# MegaMini.net
KiCad netlist of a schematic drawn in EAGLE
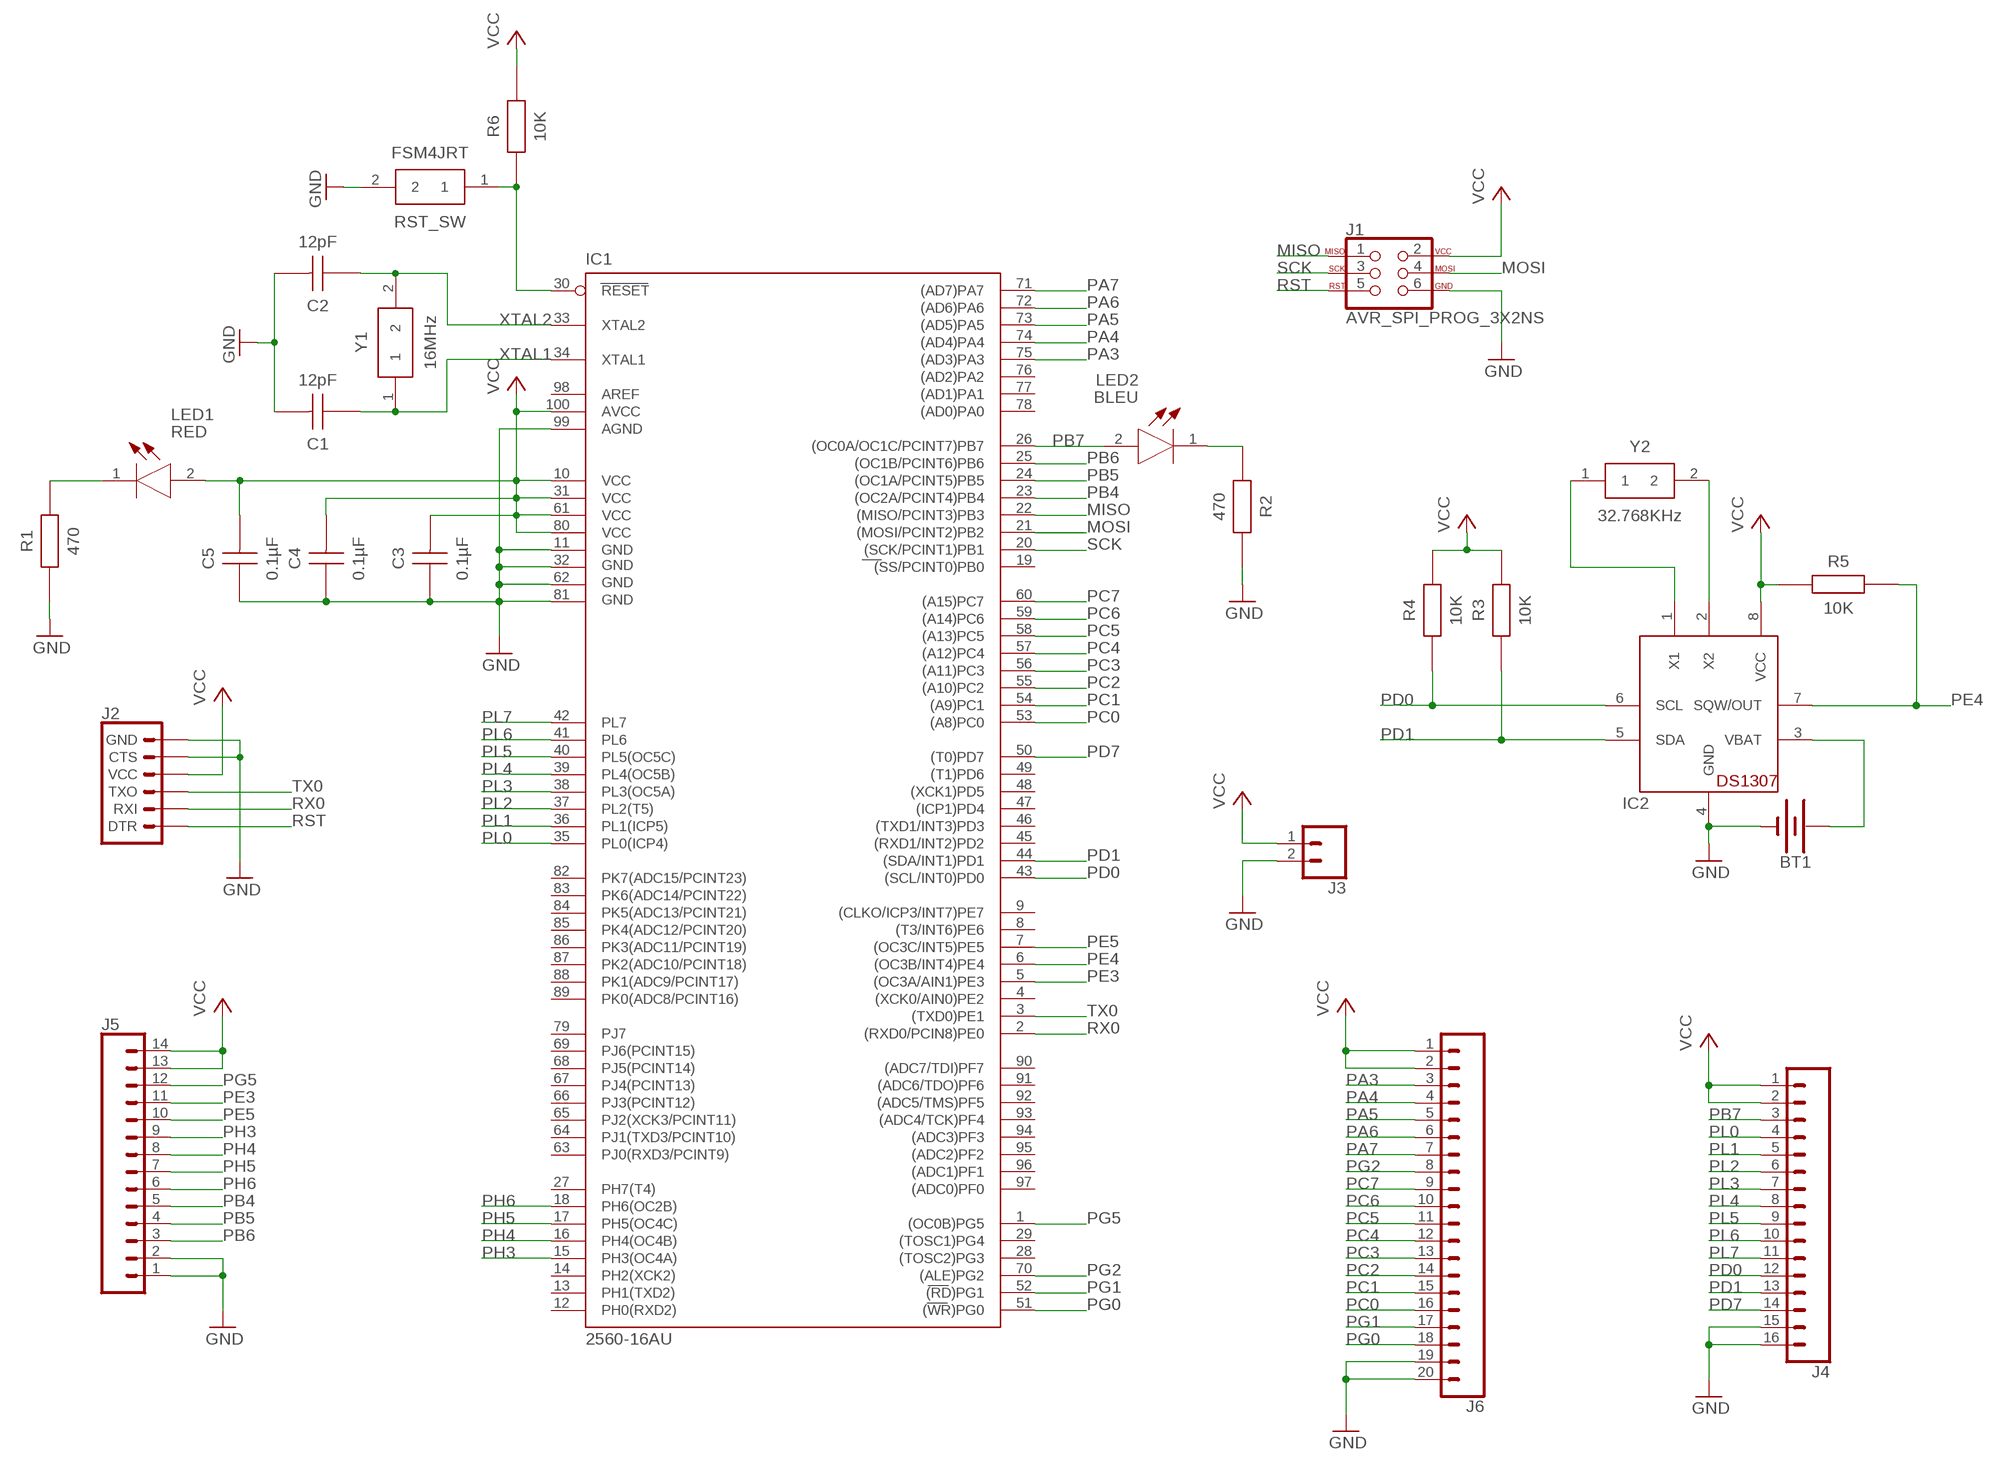
[diagram p0: schematic, sheet 1]

(export (version "E")
  (design (tool "Eeschema 10.0.6"))
  (components
    (comp (ref "BT1")
      (value "BATTERY-12MM_PTH")
      (footprint "eagle-import:BATTCON_12MM_PTH")
      (libsource (lib "eagle-import") (part "BATTERY-12MM_PTH"))
    )
    (comp (ref "C1")
      (value "12pF")
      (footprint "eagle-import:CAPC3216X88N")
      (fields
        (field (name "MANUFACTURER_PART_NUMBER") "C1206C120J5GACTU")
        (field (name "RS_PART_NUMBER") "8029986P")
      )
      (libsource (lib "eagle-import") (part "C1206C120J5GACTU"))
    )
    (comp (ref "C2")
      (value "12pF")
      (footprint "eagle-import:CAPC3216X88N")
      (fields
        (field (name "MANUFACTURER_PART_NUMBER") "C1206C120J5GACTU")
        (field (name "RS_PART_NUMBER") "8029986P")
      )
      (libsource (lib "eagle-import") (part "C1206C120J5GACTU"))
    )
    (comp (ref "C3")
      (value "0.1µF")
      (footprint "eagle-import:CAPC3216X88N")
      (fields
        (field (name "MANUFACTURER_PART_NUMBER") "C1206C104K5RACTU")
        (field (name "RS_PART_NUMBER") "2644179P")
      )
      (libsource (lib "eagle-import") (part "C1206C104K5RACTU"))
    )
    (comp (ref "C4")
      (value "0.1µF")
      (footprint "eagle-import:CAPC3216X88N")
      (fields
        (field (name "MANUFACTURER_PART_NUMBER") "C1206C104K5RACTU")
        (field (name "RS_PART_NUMBER") "2644179P")
      )
      (libsource (lib "eagle-import") (part "C1206C104K5RACTU"))
    )
    (comp (ref "C5")
      (value "0.1µF")
      (footprint "eagle-import:CAPC3216X88N")
      (fields
        (field (name "MANUFACTURER_PART_NUMBER") "C1206C104K5RACTU")
        (field (name "RS_PART_NUMBER") "2644179P")
      )
      (libsource (lib "eagle-import") (part "C1206C104K5RACTU"))
    )
    (comp (ref "IC1")
      (value "2560-16AU")
      (footprint "eagle-import:TQFP100")
      (libsource (lib "eagle-import") (part "ATMEGAAU2560-16"))
    )
    (comp (ref "IC2")
      (value "DS1307")
      (footprint "eagle-import:DIL08")
      (libsource (lib "eagle-import") (part "DS1307"))
    )
    (comp (ref "J1")
      (value "AVR_SPI_PROG_3X2NS")
      (footprint "eagle-import:2X3-NS")
      (libsource (lib "eagle-import") (part "AVR_SPI_PROG_3X2NS"))
    )
    (comp (ref "J2")
      (value "6_PIN_SERIAL_TARGET")
      (footprint "eagle-import:1X06")
      (libsource (lib "eagle-import") (part "6_PIN_SERIAL_TARGET"))
    )
    (comp (ref "J3")
      (value "CONN_02")
      (footprint "eagle-import:1X02")
      (libsource (lib "eagle-import") (part "CONN_02"))
    )
    (comp (ref "J4")
      (value "CONN_16")
      (footprint "eagle-import:1X16")
      (libsource (lib "eagle-import") (part "CONN_16"))
    )
    (comp (ref "J5")
      (value "CONN_14")
      (footprint "eagle-import:1X14")
      (libsource (lib "eagle-import") (part "CONN_14"))
    )
    (comp (ref "J6")
      (value "CONN_20")
      (footprint "eagle-import:1X20")
      (libsource (lib "eagle-import") (part "CONN_20"))
    )
    (comp (ref "LED1")
      (value "RED")
      (footprint "eagle-import:LEDC1608X80N")
      (fields (field (name "MANUFACTURER_PART_NUMBER") "150060RS75000"))
      (libsource (lib "eagle-import") (part "150060RS75000"))
    )
    (comp (ref "LED2")
      (value "BLEU")
      (footprint "eagle-import:LEDC3214X78N")
      (fields
        (field (name "MANUFACTURER_PART_NUMBER") "150120BS75000")
        (field (name "RS_PART_NUMBER") "8154243")
      )
      (libsource (lib "eagle-import") (part "150120BS75000"))
    )
    (comp (ref "R1")
      (value "470")
      (footprint "eagle-import:RESC3116X70N")
      (fields
        (field (name "MANUFACTURER_PART_NUMBER") "ERJ8ENF4700V")
        (field (name "RS_PART_NUMBER") "1142909")
      )
      (libsource (lib "eagle-import") (part "ERJ8ENF4700V"))
    )
    (comp (ref "R2")
      (value "470")
      (footprint "eagle-import:RESC3116X70N")
      (fields
        (field (name "MANUFACTURER_PART_NUMBER") "ERJ8ENF4700V")
        (field (name "RS_PART_NUMBER") "1142909")
      )
      (libsource (lib "eagle-import") (part "ERJ8ENF4700V"))
    )
    (comp (ref "R3")
      (value "10K")
      (footprint "eagle-import:RESC3116X70N")
      (fields (field (name "MANUFACTURER_PART_NUMBER") "ERJ-8ENF1002V"))
      (libsource (lib "eagle-import") (part "ERJ-8ENF1002V"))
    )
    (comp (ref "R4")
      (value "10K")
      (footprint "eagle-import:RESC3116X70N")
      (fields (field (name "MANUFACTURER_PART_NUMBER") "ERJ-8ENF1002V"))
      (libsource (lib "eagle-import") (part "ERJ-8ENF1002V"))
    )
    (comp (ref "R5")
      (value "10K")
      (footprint "eagle-import:RESC3116X70N")
      (fields (field (name "MANUFACTURER_PART_NUMBER") "ERJ-8ENF1002V"))
      (libsource (lib "eagle-import") (part "ERJ-8ENF1002V"))
    )
    (comp (ref "R6")
      (value "10K")
      (footprint "eagle-import:RESC3116X70N")
      (fields (field (name "MANUFACTURER_PART_NUMBER") "ERJ-8ENF1002V"))
      (libsource (lib "eagle-import") (part "ERJ-8ENF1002V"))
    )
    (comp (ref "RST_SW")
      (value "FSM4JRT")
      (footprint "eagle-import:FSM4JRT")
      (fields (field (name "RS_PART_NUMBER") "7182415P"))
      (libsource (lib "eagle-import") (part "FSM4JRT"))
    )
    (comp (ref "Y1")
      (value "16MHz")
      (footprint "eagle-import:FOXSDLF_120-20")
      (fields
        (field (name "MANUFACTURER_PART_NUMBER") "FOXSDLF/160-20")
        (field (name "RS_PART_NUMBER") "5476531")
      )
      (libsource (lib "eagle-import") (part "FOXSDLF_160-20"))
    )
    (comp (ref "Y2")
      (value "32.768KHz")
      (footprint "eagle-import:FC-135")
      (fields (field (name "MANUFACTURER_PART_NUMBER") "Q13FC13500004 FC-135 32.768KHZ 12.5PF"))
      (libsource (lib "eagle-import") (part "Q13FC13500004_FC-135_32.768KHZ"))
    )
  )
  (nets
    (net (code "1") (name "/MISO") (class "Default")
      (node (ref "IC1") (pin "22") (pinfunction "(MISO/PCINT3)PB3_22") (pintype "bidirectional"))
      (node (ref "J1") (pin "1") (pinfunction "1_1") (pintype "passive"))
    )
    (net (code "2") (name "/MOSI") (class "Default")
      (node (ref "IC1") (pin "21") (pinfunction "(MOSI/PCINT2)PB2_21") (pintype "bidirectional"))
      (node (ref "J1") (pin "4") (pinfunction "4_4") (pintype "passive"))
    )
    (net (code "3") (name "/PA3") (class "Default")
      (node (ref "IC1") (pin "75") (pinfunction "(AD3)PA3_75") (pintype "bidirectional"))
      (node (ref "J6") (pin "3") (pinfunction "3_3") (pintype "passive"))
    )
    (net (code "4") (name "/PA4") (class "Default")
      (node (ref "IC1") (pin "74") (pinfunction "(AD4)PA4_74") (pintype "bidirectional"))
      (node (ref "J6") (pin "4") (pinfunction "4_4") (pintype "passive"))
    )
    (net (code "5") (name "/PA5") (class "Default")
      (node (ref "IC1") (pin "73") (pinfunction "(AD5)PA5_73") (pintype "bidirectional"))
      (node (ref "J6") (pin "5") (pinfunction "5_5") (pintype "passive"))
    )
    (net (code "6") (name "/PA6") (class "Default")
      (node (ref "IC1") (pin "72") (pinfunction "(AD6)PA6_72") (pintype "bidirectional"))
      (node (ref "J6") (pin "6") (pinfunction "6_6") (pintype "passive"))
    )
    (net (code "7") (name "/PA7") (class "Default")
      (node (ref "IC1") (pin "71") (pinfunction "(AD7)PA7_71") (pintype "bidirectional"))
      (node (ref "J6") (pin "7") (pinfunction "7_7") (pintype "passive"))
    )
    (net (code "8") (name "/PB4") (class "Default")
      (node (ref "IC1") (pin "23") (pinfunction "(OC2A/PCINT4)PB4_23") (pintype "bidirectional"))
      (node (ref "J5") (pin "5") (pinfunction "5_5") (pintype "passive"))
    )
    (net (code "9") (name "/PB5") (class "Default")
      (node (ref "IC1") (pin "24") (pinfunction "(OC1A/PCINT5)PB5_24") (pintype "bidirectional"))
      (node (ref "J5") (pin "4") (pinfunction "4_4") (pintype "passive"))
    )
    (net (code "10") (name "/PB6") (class "Default")
      (node (ref "IC1") (pin "25") (pinfunction "(OC1B/PCINT6)PB6_25") (pintype "bidirectional"))
      (node (ref "J5") (pin "3") (pinfunction "3_3") (pintype "passive"))
    )
    (net (code "11") (name "/PB7") (class "Default")
      (node (ref "IC1") (pin "26") (pinfunction "(OC0A/OC1C/PCINT7)PB7_26") (pintype "bidirectional"))
      (node (ref "J4") (pin "3") (pinfunction "3_3") (pintype "passive"))
      (node (ref "LED2") (pin "2") (pinfunction "A_2") (pintype "input"))
    )
    (net (code "12") (name "/PC0") (class "Default")
      (node (ref "IC1") (pin "53") (pinfunction "(A8)PC0_53") (pintype "bidirectional"))
      (node (ref "J6") (pin "16") (pinfunction "16_16") (pintype "passive"))
    )
    (net (code "13") (name "/PC1") (class "Default")
      (node (ref "IC1") (pin "54") (pinfunction "(A9)PC1_54") (pintype "bidirectional"))
      (node (ref "J6") (pin "15") (pinfunction "15_15") (pintype "passive"))
    )
    (net (code "14") (name "/PC2") (class "Default")
      (node (ref "IC1") (pin "55") (pinfunction "(A10)PC2_55") (pintype "bidirectional"))
      (node (ref "J6") (pin "14") (pinfunction "14_14") (pintype "passive"))
    )
    (net (code "15") (name "/PC3") (class "Default")
      (node (ref "IC1") (pin "56") (pinfunction "(A11)PC3_56") (pintype "bidirectional"))
      (node (ref "J6") (pin "13") (pinfunction "13_13") (pintype "passive"))
    )
    (net (code "16") (name "/PC4") (class "Default")
      (node (ref "IC1") (pin "57") (pinfunction "(A12)PC4_57") (pintype "bidirectional"))
      (node (ref "J6") (pin "12") (pinfunction "12_12") (pintype "passive"))
    )
    (net (code "17") (name "/PC5") (class "Default")
      (node (ref "IC1") (pin "58") (pinfunction "(A13)PC5_58") (pintype "bidirectional"))
      (node (ref "J6") (pin "11") (pinfunction "11_11") (pintype "passive"))
    )
    (net (code "18") (name "/PC6") (class "Default")
      (node (ref "IC1") (pin "59") (pinfunction "(A14)PC6_59") (pintype "bidirectional"))
      (node (ref "J6") (pin "10") (pinfunction "10_10") (pintype "passive"))
    )
    (net (code "19") (name "/PC7") (class "Default")
      (node (ref "IC1") (pin "60") (pinfunction "(A15)PC7_60") (pintype "bidirectional"))
      (node (ref "J6") (pin "9") (pinfunction "9_9") (pintype "passive"))
    )
    (net (code "20") (name "/PD0") (class "Default")
      (node (ref "IC1") (pin "43") (pinfunction "(SCL/INT0)PD0_43") (pintype "bidirectional"))
      (node (ref "IC2") (pin "6") (pinfunction "SCL_6") (pintype "bidirectional"))
      (node (ref "J4") (pin "12") (pinfunction "12_12") (pintype "passive"))
      (node (ref "R4") (pin "1") (pinfunction "1_1") (pintype "bidirectional"))
    )
    (net (code "21") (name "/PD1") (class "Default")
      (node (ref "IC1") (pin "44") (pinfunction "(SDA/INT1)PD1_44") (pintype "bidirectional"))
      (node (ref "IC2") (pin "5") (pinfunction "SDA_5") (pintype "bidirectional"))
      (node (ref "J4") (pin "13") (pinfunction "13_13") (pintype "passive"))
      (node (ref "R3") (pin "1") (pinfunction "1_1") (pintype "bidirectional"))
    )
    (net (code "22") (name "/PD7") (class "Default")
      (node (ref "IC1") (pin "50") (pinfunction "(T0)PD7_50") (pintype "bidirectional"))
      (node (ref "J4") (pin "14") (pinfunction "14_14") (pintype "passive"))
    )
    (net (code "23") (name "/PE3") (class "Default")
      (node (ref "IC1") (pin "5") (pinfunction "(OC3A/AIN1)PE3_5") (pintype "bidirectional"))
      (node (ref "J5") (pin "11") (pinfunction "11_11") (pintype "passive"))
    )
    (net (code "24") (name "/PE4") (class "Default")
      (node (ref "IC1") (pin "6") (pinfunction "(OC3B/INT4)PE4_6") (pintype "bidirectional"))
      (node (ref "IC2") (pin "7") (pinfunction "SQW/OUT_7") (pintype "bidirectional"))
      (node (ref "R5") (pin "2") (pinfunction "2_2") (pintype "bidirectional"))
    )
    (net (code "25") (name "/PE5") (class "Default")
      (node (ref "IC1") (pin "7") (pinfunction "(OC3C/INT5)PE5_7") (pintype "bidirectional"))
      (node (ref "J5") (pin "10") (pinfunction "10_10") (pintype "passive"))
    )
    (net (code "26") (name "/PG0") (class "Default")
      (node (ref "IC1") (pin "51") (pinfunction "(WR)PG0_51") (pintype "bidirectional"))
      (node (ref "J6") (pin "18") (pinfunction "18_18") (pintype "passive"))
    )
    (net (code "27") (name "/PG1") (class "Default")
      (node (ref "IC1") (pin "52") (pinfunction "(RD)PG1_52") (pintype "bidirectional"))
      (node (ref "J6") (pin "17") (pinfunction "17_17") (pintype "passive"))
    )
    (net (code "28") (name "/PG2") (class "Default")
      (node (ref "IC1") (pin "70") (pinfunction "(ALE)PG2_70") (pintype "bidirectional"))
      (node (ref "J6") (pin "8") (pinfunction "8_8") (pintype "passive"))
    )
    (net (code "29") (name "/PG5") (class "Default")
      (node (ref "IC1") (pin "1") (pinfunction "(OC0B)PG5_1") (pintype "bidirectional"))
      (node (ref "J5") (pin "12") (pinfunction "12_12") (pintype "passive"))
    )
    (net (code "30") (name "/PH3") (class "Default")
      (node (ref "IC1") (pin "15") (pinfunction "PH3(OC4A)_15") (pintype "bidirectional"))
      (node (ref "J5") (pin "9") (pinfunction "9_9") (pintype "passive"))
    )
    (net (code "31") (name "/PH4") (class "Default")
      (node (ref "IC1") (pin "16") (pinfunction "PH4(OC4B)_16") (pintype "bidirectional"))
      (node (ref "J5") (pin "8") (pinfunction "8_8") (pintype "passive"))
    )
    (net (code "32") (name "/PH5") (class "Default")
      (node (ref "IC1") (pin "17") (pinfunction "PH5(OC4C)_17") (pintype "bidirectional"))
      (node (ref "J5") (pin "7") (pinfunction "7_7") (pintype "passive"))
    )
    (net (code "33") (name "/PH6") (class "Default")
      (node (ref "IC1") (pin "18") (pinfunction "PH6(OC2B)_18") (pintype "bidirectional"))
      (node (ref "J5") (pin "6") (pinfunction "6_6") (pintype "passive"))
    )
    (net (code "34") (name "/PL0") (class "Default")
      (node (ref "IC1") (pin "35") (pinfunction "PL0(ICP4)_35") (pintype "bidirectional"))
      (node (ref "J4") (pin "4") (pinfunction "4_4") (pintype "passive"))
    )
    (net (code "35") (name "/PL1") (class "Default")
      (node (ref "IC1") (pin "36") (pinfunction "PL1(ICP5)_36") (pintype "bidirectional"))
      (node (ref "J4") (pin "5") (pinfunction "5_5") (pintype "passive"))
    )
    (net (code "36") (name "/PL2") (class "Default")
      (node (ref "IC1") (pin "37") (pinfunction "PL2(T5)_37") (pintype "bidirectional"))
      (node (ref "J4") (pin "6") (pinfunction "6_6") (pintype "passive"))
    )
    (net (code "37") (name "/PL3") (class "Default")
      (node (ref "IC1") (pin "38") (pinfunction "PL3(OC5A)_38") (pintype "bidirectional"))
      (node (ref "J4") (pin "7") (pinfunction "7_7") (pintype "passive"))
    )
    (net (code "38") (name "/PL4") (class "Default")
      (node (ref "IC1") (pin "39") (pinfunction "PL4(OC5B)_39") (pintype "bidirectional"))
      (node (ref "J4") (pin "8") (pinfunction "8_8") (pintype "passive"))
    )
    (net (code "39") (name "/PL5") (class "Default")
      (node (ref "IC1") (pin "40") (pinfunction "PL5(OC5C)_40") (pintype "bidirectional"))
      (node (ref "J4") (pin "9") (pinfunction "9_9") (pintype "passive"))
    )
    (net (code "40") (name "/PL6") (class "Default")
      (node (ref "IC1") (pin "41") (pinfunction "PL6_41") (pintype "bidirectional"))
      (node (ref "J4") (pin "10") (pinfunction "10_10") (pintype "passive"))
    )
    (net (code "41") (name "/PL7") (class "Default")
      (node (ref "IC1") (pin "42") (pinfunction "PL7_42") (pintype "bidirectional"))
      (node (ref "J4") (pin "11") (pinfunction "11_11") (pintype "passive"))
    )
    (net (code "42") (name "/RST") (class "Default")
      (node (ref "J1") (pin "5") (pinfunction "5_5") (pintype "passive"))
      (node (ref "J2") (pin "1") (pinfunction "DTR_1") (pintype "passive"))
    )
    (net (code "43") (name "/RX0") (class "Default")
      (node (ref "IC1") (pin "2") (pinfunction "(RXD0/PCIN8)PE0_2") (pintype "bidirectional"))
      (node (ref "J2") (pin "2") (pinfunction "RXI_2") (pintype "passive"))
    )
    (net (code "44") (name "/SCK") (class "Default")
      (node (ref "IC1") (pin "20") (pinfunction "(SCK/PCINT1)PB1_20") (pintype "bidirectional"))
      (node (ref "J1") (pin "3") (pinfunction "3_3") (pintype "passive"))
    )
    (net (code "45") (name "/TX0") (class "Default")
      (node (ref "IC1") (pin "3") (pinfunction "(TXD0)PE1_3") (pintype "bidirectional"))
      (node (ref "J2") (pin "3") (pinfunction "TXO_3") (pintype "passive"))
    )
    (net (code "46") (name "/XTAL1") (class "Default")
      (node (ref "C1") (pin "1") (pinfunction "1_1") (pintype "bidirectional"))
      (node (ref "IC1") (pin "34") (pinfunction "XTAL1_34") (pintype "input"))
      (node (ref "Y1") (pin "1") (pinfunction "1_1") (pintype "passive"))
    )
    (net (code "47") (name "/XTAL2") (class "Default")
      (node (ref "C2") (pin "1") (pinfunction "1_1") (pintype "bidirectional"))
      (node (ref "IC1") (pin "33") (pinfunction "XTAL2_33") (pintype "output"))
      (node (ref "Y1") (pin "2") (pinfunction "2_2") (pintype "passive"))
    )
    (net (code "48") (name "GND") (class "Default")
      (node (ref "BT1") (pin "GND") (pinfunction "-_GND") (pintype "power_in"))
      (node (ref "C1") (pin "2") (pinfunction "2_2") (pintype "bidirectional"))
      (node (ref "C2") (pin "2") (pinfunction "2_2") (pintype "bidirectional"))
      (node (ref "C3") (pin "1") (pinfunction "1_1") (pintype "bidirectional"))
      (node (ref "C4") (pin "1") (pinfunction "1_1") (pintype "bidirectional"))
      (node (ref "C5") (pin "1") (pinfunction "1_1") (pintype "bidirectional"))
      (node (ref "IC1") (pin "11") (pinfunction "GND_11") (pintype "power_in"))
      (node (ref "IC1") (pin "32") (pinfunction "GND1_32") (pintype "power_in"))
      (node (ref "IC1") (pin "62") (pinfunction "GND2_62") (pintype "power_in"))
      (node (ref "IC1") (pin "81") (pinfunction "GND3_81") (pintype "power_in"))
      (node (ref "IC1") (pin "99") (pinfunction "AGND_99") (pintype "power_in"))
      (node (ref "IC2") (pin "4") (pinfunction "GND_4") (pintype "power_in"))
      (node (ref "J1") (pin "6") (pinfunction "6_6") (pintype "passive"))
      (node (ref "J2") (pin "5") (pinfunction "CTS_5") (pintype "passive"))
      (node (ref "J2") (pin "6") (pinfunction "GND_6") (pintype "passive"))
      (node (ref "J3") (pin "2") (pinfunction "2_2") (pintype "passive"))
      (node (ref "J4") (pin "15") (pinfunction "15_15") (pintype "passive"))
      (node (ref "J4") (pin "16") (pinfunction "16_16") (pintype "passive"))
      (node (ref "J5") (pin "1") (pinfunction "1_1") (pintype "passive"))
      (node (ref "J5") (pin "2") (pinfunction "2_2") (pintype "passive"))
      (node (ref "J6") (pin "19") (pinfunction "19_19") (pintype "passive"))
      (node (ref "J6") (pin "20") (pinfunction "20_20") (pintype "passive"))
      (node (ref "R1") (pin "1") (pinfunction "1_1") (pintype "bidirectional"))
      (node (ref "R2") (pin "2") (pinfunction "2_2") (pintype "bidirectional"))
      (node (ref "RST_SW") (pin "2") (pinfunction "2_2") (pintype "passive"))
    )
    (net (code "49") (name "Net-(BT1-+)") (class "Default")
      (node (ref "BT1") (pin "VCC@1") (pinfunction "+_VCC@1") (pintype "power_in"))
      (node (ref "IC2") (pin "3") (pinfunction "VBAT_3") (pintype "power_in"))
    )
    (net (code "50") (name "Net-(IC1-RESET)") (class "Default")
      (node (ref "IC1") (pin "30") (pinfunction "RESET_30") (pintype "input"))
      (node (ref "R6") (pin "1") (pinfunction "1_1") (pintype "bidirectional"))
      (node (ref "RST_SW") (pin "1") (pinfunction "1_1") (pintype "passive"))
    )
    (net (code "51") (name "Net-(IC2-X1)") (class "Default")
      (node (ref "IC2") (pin "1") (pinfunction "X1_1") (pintype "passive"))
      (node (ref "Y2") (pin "1") (pinfunction "1_1") (pintype "passive"))
    )
    (net (code "52") (name "Net-(IC2-X2)") (class "Default")
      (node (ref "IC2") (pin "2") (pinfunction "X2_2") (pintype "passive"))
      (node (ref "Y2") (pin "2") (pinfunction "2_2") (pintype "passive"))
    )
    (net (code "53") (name "Net-(LED1-K)") (class "Default")
      (node (ref "LED1") (pin "1") (pinfunction "K_1") (pintype "input"))
      (node (ref "R1") (pin "2") (pinfunction "2_2") (pintype "bidirectional"))
    )
    (net (code "54") (name "Net-(LED2-K)") (class "Default")
      (node (ref "LED2") (pin "1") (pinfunction "K_1") (pintype "input"))
      (node (ref "R2") (pin "1") (pinfunction "1_1") (pintype "bidirectional"))
    )
    (net (code "55") (name "VCC") (class "Default")
      (node (ref "C3") (pin "2") (pinfunction "2_2") (pintype "bidirectional"))
      (node (ref "C4") (pin "2") (pinfunction "2_2") (pintype "bidirectional"))
      (node (ref "C5") (pin "2") (pinfunction "2_2") (pintype "bidirectional"))
      (node (ref "IC1") (pin "10") (pinfunction "VCC_10") (pintype "power_in"))
      (node (ref "IC1") (pin "100") (pinfunction "AVCC_100") (pintype "power_in"))
      (node (ref "IC1") (pin "31") (pinfunction "VCC1_31") (pintype "power_in"))
      (node (ref "IC1") (pin "61") (pinfunction "VCC2_61") (pintype "power_in"))
      (node (ref "IC1") (pin "80") (pinfunction "VCC3_80") (pintype "power_in"))
      (node (ref "IC2") (pin "8") (pinfunction "VCC_8") (pintype "power_in"))
      (node (ref "J1") (pin "2") (pinfunction "2_2") (pintype "passive"))
      (node (ref "J2") (pin "4") (pinfunction "VCC_4") (pintype "passive"))
      (node (ref "J3") (pin "1") (pinfunction "1_1") (pintype "passive"))
      (node (ref "J4") (pin "1") (pinfunction "1_1") (pintype "passive"))
      (node (ref "J4") (pin "2") (pinfunction "2_2") (pintype "passive"))
      (node (ref "J5") (pin "13") (pinfunction "13_13") (pintype "passive"))
      (node (ref "J5") (pin "14") (pinfunction "14_14") (pintype "passive"))
      (node (ref "J6") (pin "1") (pinfunction "1_1") (pintype "passive"))
      (node (ref "J6") (pin "2") (pinfunction "2_2") (pintype "passive"))
      (node (ref "LED1") (pin "2") (pinfunction "A_2") (pintype "input"))
      (node (ref "R3") (pin "2") (pinfunction "2_2") (pintype "bidirectional"))
      (node (ref "R4") (pin "2") (pinfunction "2_2") (pintype "bidirectional"))
      (node (ref "R5") (pin "1") (pinfunction "1_1") (pintype "bidirectional"))
      (node (ref "R6") (pin "2") (pinfunction "2_2") (pintype "bidirectional"))
    )
    (net (code "56") (name "unconnected-(IC1-(AD0)PA0-Pad78)") (class "Default")
      (node (ref "IC1") (pin "78") (pinfunction "(AD0)PA0_78") (pintype "bidirectional"))
    )
    (net (code "57") (name "unconnected-(IC1-(AD1)PA1-Pad77)") (class "Default")
      (node (ref "IC1") (pin "77") (pinfunction "(AD1)PA1_77") (pintype "bidirectional"))
    )
    (net (code "58") (name "unconnected-(IC1-(AD2)PA2-Pad76)") (class "Default")
      (node (ref "IC1") (pin "76") (pinfunction "(AD2)PA2_76") (pintype "bidirectional"))
    )
    (net (code "59") (name "unconnected-(IC1-(ADC0)PF0-Pad97)") (class "Default")
      (node (ref "IC1") (pin "97") (pinfunction "(ADC0)PF0_97") (pintype "bidirectional"))
    )
    (net (code "60") (name "unconnected-(IC1-(ADC1)PF1-Pad96)") (class "Default")
      (node (ref "IC1") (pin "96") (pinfunction "(ADC1)PF1_96") (pintype "bidirectional"))
    )
    (net (code "61") (name "unconnected-(IC1-(ADC2)PF2-Pad95)") (class "Default")
      (node (ref "IC1") (pin "95") (pinfunction "(ADC2)PF2_95") (pintype "bidirectional"))
    )
    (net (code "62") (name "unconnected-(IC1-(ADC3)PF3-Pad94)") (class "Default")
      (node (ref "IC1") (pin "94") (pinfunction "(ADC3)PF3_94") (pintype "bidirectional"))
    )
    (net (code "63") (name "unconnected-(IC1-(ADC4{slash}TCK)PF4-Pad93)") (class "Default")
      (node (ref "IC1") (pin "93") (pinfunction "(ADC4/TCK)PF4_93") (pintype "bidirectional"))
    )
    (net (code "64") (name "unconnected-(IC1-(ADC5{slash}TMS)PF5-Pad92)") (class "Default")
      (node (ref "IC1") (pin "92") (pinfunction "(ADC5/TMS)PF5_92") (pintype "bidirectional"))
    )
    (net (code "65") (name "unconnected-(IC1-(ADC6{slash}TDO)PF6-Pad91)") (class "Default")
      (node (ref "IC1") (pin "91") (pinfunction "(ADC6/TDO)PF6_91") (pintype "bidirectional"))
    )
    (net (code "66") (name "unconnected-(IC1-(ADC7{slash}TDI)PF7-Pad90)") (class "Default")
      (node (ref "IC1") (pin "90") (pinfunction "(ADC7/TDI)PF7_90") (pintype "bidirectional"))
    )
    (net (code "67") (name "unconnected-(IC1-(CLKO{slash}ICP3{slash}INT7)PE7-Pad9)") (class "Default")
      (node (ref "IC1") (pin "9") (pinfunction "(CLKO/ICP3/INT7)PE7_9") (pintype "bidirectional"))
    )
    (net (code "68") (name "unconnected-(IC1-(ICP1)PD4-Pad47)") (class "Default")
      (node (ref "IC1") (pin "47") (pinfunction "(ICP1)PD4_47") (pintype "bidirectional"))
    )
    (net (code "69") (name "unconnected-(IC1-(RXD1{slash}INT2)PD2-Pad45)") (class "Default")
      (node (ref "IC1") (pin "45") (pinfunction "(RXD1/INT2)PD2_45") (pintype "bidirectional"))
    )
    (net (code "70") (name "unconnected-(IC1-(SS{slash}PCINT0)PB0-Pad19)") (class "Default")
      (node (ref "IC1") (pin "19") (pinfunction "(SS/PCINT0)PB0_19") (pintype "bidirectional"))
    )
    (net (code "71") (name "unconnected-(IC1-(T1)PD6-Pad49)") (class "Default")
      (node (ref "IC1") (pin "49") (pinfunction "(T1)PD6_49") (pintype "bidirectional"))
    )
    (net (code "72") (name "unconnected-(IC1-(T3{slash}INT6)PE6-Pad8)") (class "Default")
      (node (ref "IC1") (pin "8") (pinfunction "(T3/INT6)PE6_8") (pintype "bidirectional"))
    )
    (net (code "73") (name "unconnected-(IC1-(TOSC1)PG4-Pad29)") (class "Default")
      (node (ref "IC1") (pin "29") (pinfunction "(TOSC1)PG4_29") (pintype "bidirectional"))
    )
    (net (code "74") (name "unconnected-(IC1-(TOSC2)PG3-Pad28)") (class "Default")
      (node (ref "IC1") (pin "28") (pinfunction "(TOSC2)PG3_28") (pintype "bidirectional"))
    )
    (net (code "75") (name "unconnected-(IC1-(TXD1{slash}INT3)PD3-Pad46)") (class "Default")
      (node (ref "IC1") (pin "46") (pinfunction "(TXD1/INT3)PD3_46") (pintype "bidirectional"))
    )
    (net (code "76") (name "unconnected-(IC1-(XCK0{slash}AIN0)PE2-Pad4)") (class "Default")
      (node (ref "IC1") (pin "4") (pinfunction "(XCK0/AIN0)PE2_4") (pintype "bidirectional"))
    )
    (net (code "77") (name "unconnected-(IC1-(XCK1)PD5-Pad48)") (class "Default")
      (node (ref "IC1") (pin "48") (pinfunction "(XCK1)PD5_48") (pintype "bidirectional"))
    )
    (net (code "78") (name "unconnected-(IC1-AREF-Pad98)") (class "Default")
      (node (ref "IC1") (pin "98") (pinfunction "AREF_98") (pintype "bidirectional"))
    )
    (net (code "79") (name "unconnected-(IC1-PH0(RXD2)-Pad12)") (class "Default")
      (node (ref "IC1") (pin "12") (pinfunction "PH0(RXD2)_12") (pintype "bidirectional"))
    )
    (net (code "80") (name "unconnected-(IC1-PH1(TXD2)-Pad13)") (class "Default")
      (node (ref "IC1") (pin "13") (pinfunction "PH1(TXD2)_13") (pintype "bidirectional"))
    )
    (net (code "81") (name "unconnected-(IC1-PH2(XCK2)-Pad14)") (class "Default")
      (node (ref "IC1") (pin "14") (pinfunction "PH2(XCK2)_14") (pintype "bidirectional"))
    )
    (net (code "82") (name "unconnected-(IC1-PH7(T4)-Pad27)") (class "Default")
      (node (ref "IC1") (pin "27") (pinfunction "PH7(T4)_27") (pintype "bidirectional"))
    )
    (net (code "83") (name "unconnected-(IC1-PJ0(RXD3{slash}PCINT9)-Pad63)") (class "Default")
      (node (ref "IC1") (pin "63") (pinfunction "PJ0(RXD3/PCINT9)_63") (pintype "bidirectional"))
    )
    (net (code "84") (name "unconnected-(IC1-PJ1(TXD3{slash}PCINT10)-Pad64)") (class "Default")
      (node (ref "IC1") (pin "64") (pinfunction "PJ1(TXD3/PCINT10)_64") (pintype "bidirectional"))
    )
    (net (code "85") (name "unconnected-(IC1-PJ2(XCK3{slash}PCINT11)-Pad65)") (class "Default")
      (node (ref "IC1") (pin "65") (pinfunction "PJ2(XCK3/PCINT11)_65") (pintype "bidirectional"))
    )
    (net (code "86") (name "unconnected-(IC1-PJ3(PCINT12)-Pad66)") (class "Default")
      (node (ref "IC1") (pin "66") (pinfunction "PJ3(PCINT12)_66") (pintype "bidirectional"))
    )
    (net (code "87") (name "unconnected-(IC1-PJ4(PCINT13)-Pad67)") (class "Default")
      (node (ref "IC1") (pin "67") (pinfunction "PJ4(PCINT13)_67") (pintype "bidirectional"))
    )
    (net (code "88") (name "unconnected-(IC1-PJ5(PCINT14)-Pad68)") (class "Default")
      (node (ref "IC1") (pin "68") (pinfunction "PJ5(PCINT14)_68") (pintype "bidirectional"))
    )
    (net (code "89") (name "unconnected-(IC1-PJ6(PCINT15)-Pad69)") (class "Default")
      (node (ref "IC1") (pin "69") (pinfunction "PJ6(PCINT15)_69") (pintype "bidirectional"))
    )
    (net (code "90") (name "unconnected-(IC1-PJ7-Pad79)") (class "Default")
      (node (ref "IC1") (pin "79") (pinfunction "PJ7_79") (pintype "bidirectional"))
    )
    (net (code "91") (name "unconnected-(IC1-PK0(ADC8{slash}PCINT16)-Pad89)") (class "Default")
      (node (ref "IC1") (pin "89") (pinfunction "PK0(ADC8/PCINT16)_89") (pintype "bidirectional"))
    )
    (net (code "92") (name "unconnected-(IC1-PK1(ADC9{slash}PCINT17)-Pad88)") (class "Default")
      (node (ref "IC1") (pin "88") (pinfunction "PK1(ADC9/PCINT17)_88") (pintype "bidirectional"))
    )
    (net (code "93") (name "unconnected-(IC1-PK2(ADC10{slash}PCINT18)-Pad87)") (class "Default")
      (node (ref "IC1") (pin "87") (pinfunction "PK2(ADC10/PCINT18)_87") (pintype "bidirectional"))
    )
    (net (code "94") (name "unconnected-(IC1-PK3(ADC11{slash}PCINT19)-Pad86)") (class "Default")
      (node (ref "IC1") (pin "86") (pinfunction "PK3(ADC11/PCINT19)_86") (pintype "bidirectional"))
    )
    (net (code "95") (name "unconnected-(IC1-PK4(ADC12{slash}PCINT20)-Pad85)") (class "Default")
      (node (ref "IC1") (pin "85") (pinfunction "PK4(ADC12/PCINT20)_85") (pintype "bidirectional"))
    )
    (net (code "96") (name "unconnected-(IC1-PK5(ADC13{slash}PCINT21)-Pad84)") (class "Default")
      (node (ref "IC1") (pin "84") (pinfunction "PK5(ADC13/PCINT21)_84") (pintype "bidirectional"))
    )
    (net (code "97") (name "unconnected-(IC1-PK6(ADC14{slash}PCINT22)-Pad83)") (class "Default")
      (node (ref "IC1") (pin "83") (pinfunction "PK6(ADC14/PCINT22)_83") (pintype "bidirectional"))
    )
    (net (code "98") (name "unconnected-(IC1-PK7(ADC15{slash}PCINT23)-Pad82)") (class "Default")
      (node (ref "IC1") (pin "82") (pinfunction "PK7(ADC15/PCINT23)_82") (pintype "bidirectional"))
    )
  )
)
